# MSP_Telemetry.net
KiCad netlist of a schematic drawn in Altium Designer
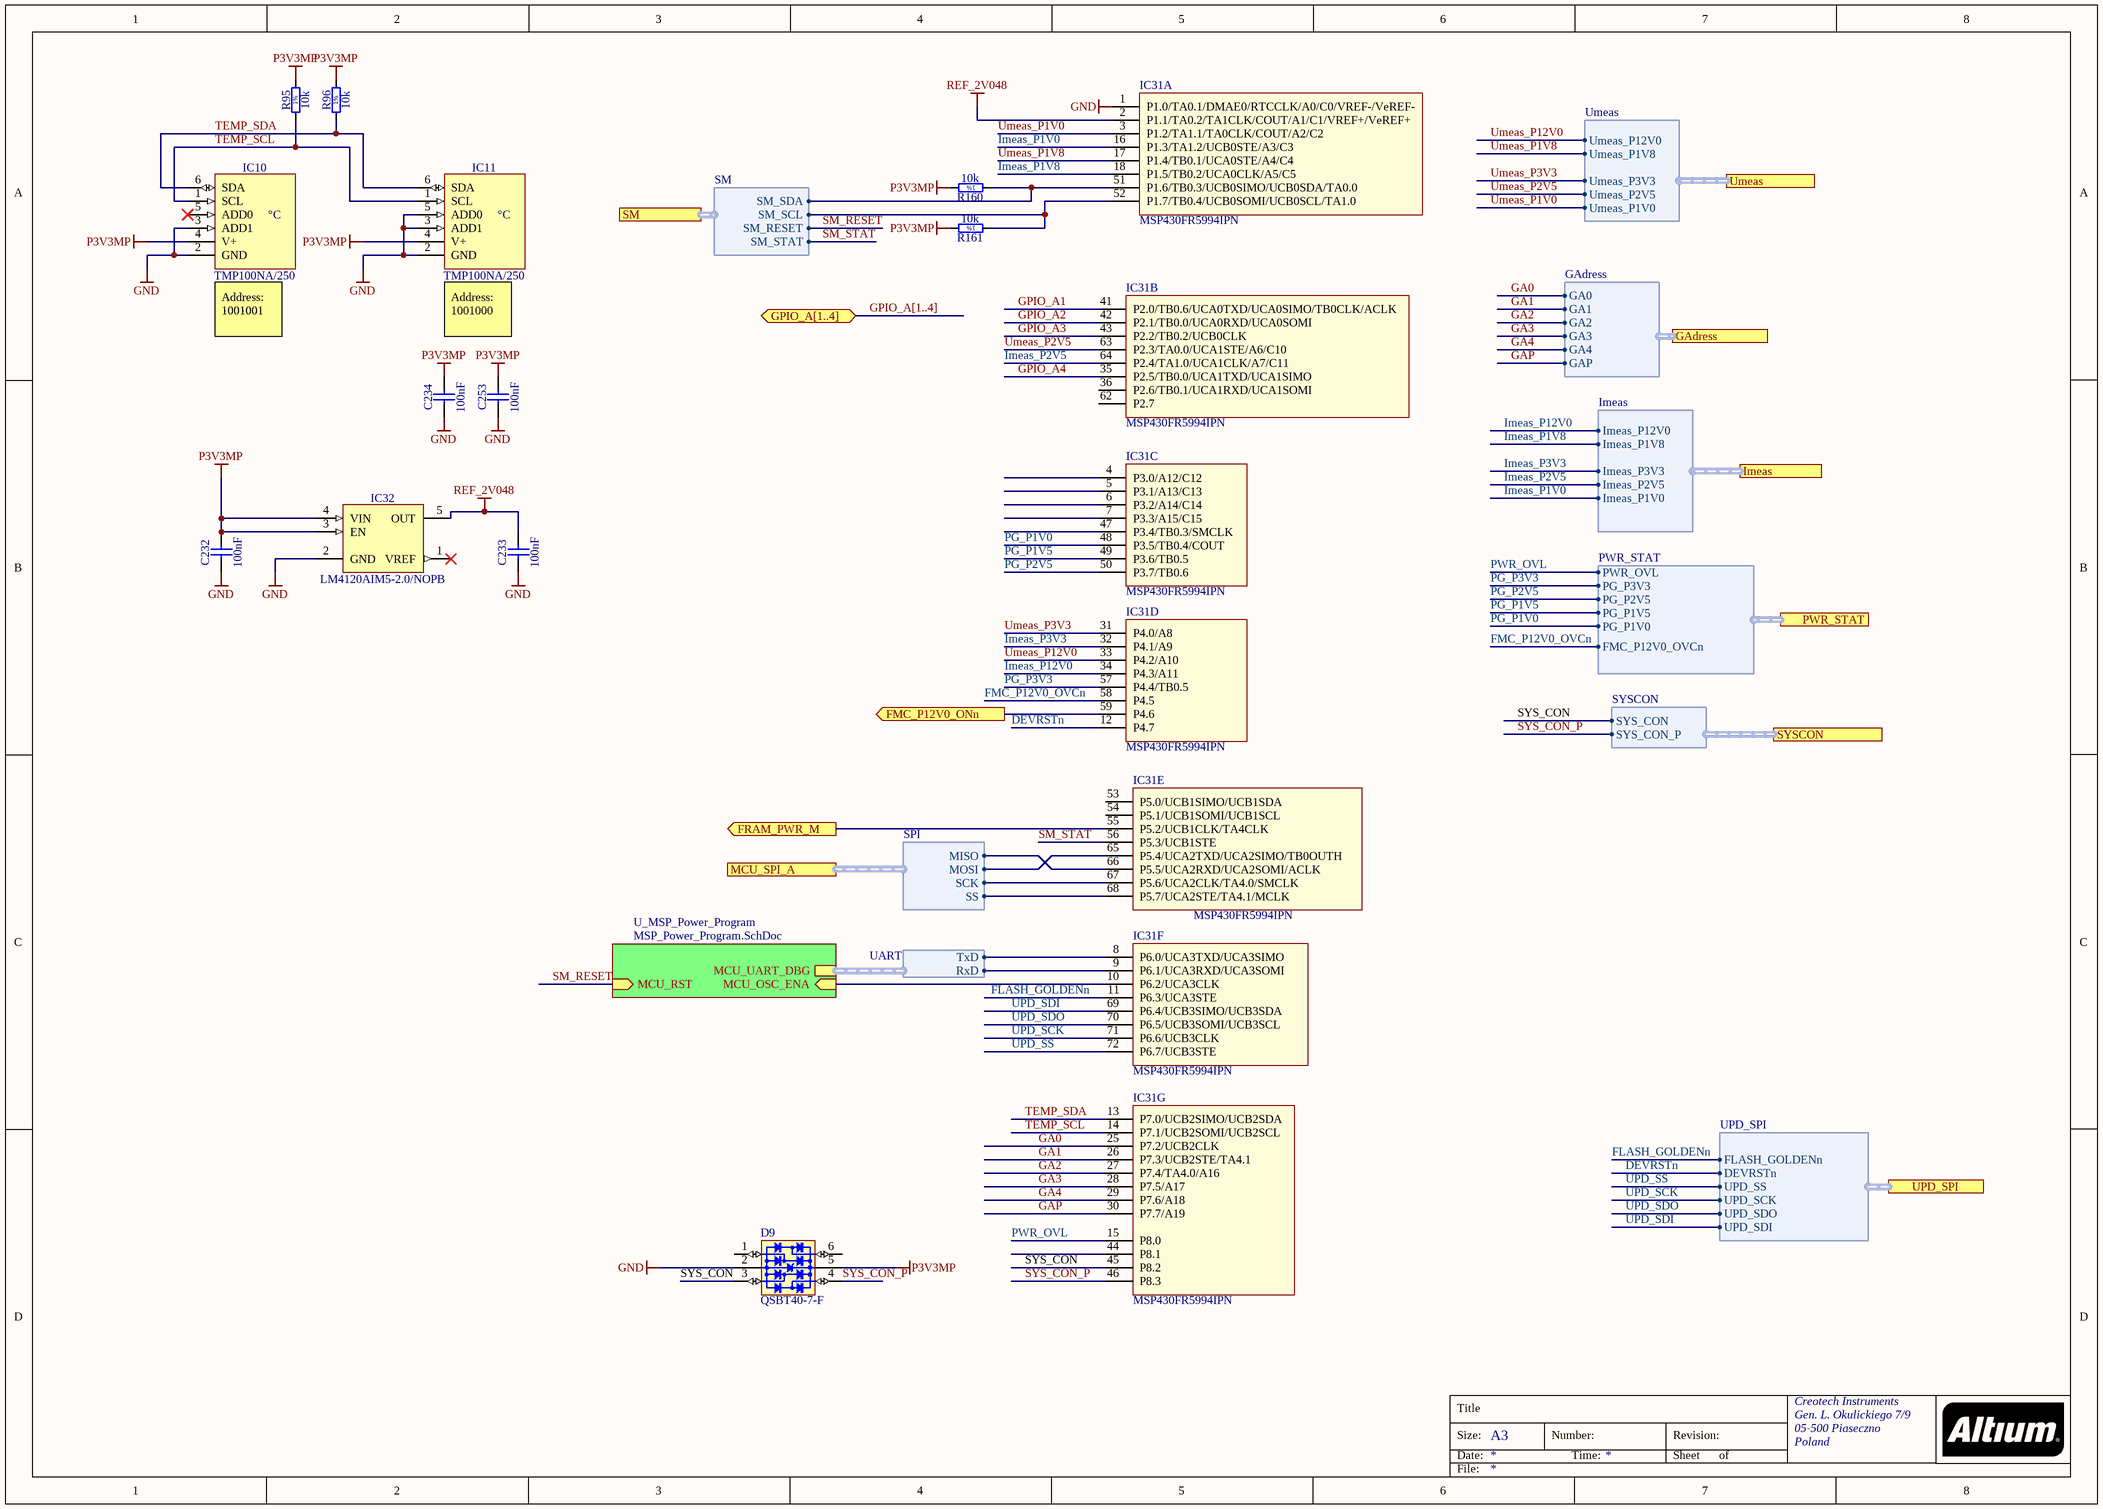
[diagram p0: MSP_Telemetry.SchDoc]

(export (version "E")
  (design (tool "Eeschema 10.0.6"))
  (components
    (comp (ref "C232")
      (value "100nF")
      (footprint "CAPC1005X55N")
      (description "Non-polarised capacitor")
      (fields
        (field (name "PART NUMBER") "CC0402_100NF_25V_10%_X7R_YUDEN_TMK105B7104KVHF")
        (field (name "VOLTAGE") "25V")
        (field (name "AUTHOR") "CERN DEM JLC")
      )
      (libsource (lib "Capacitors") (part "Capacitor - non polarized"))
    )
    (comp (ref "C233")
      (value "100nF")
      (footprint "CAPC1005X55N")
      (description "Non-polarised capacitor")
      (fields
        (field (name "PART NUMBER") "CC0402_100NF_25V_10%_X7R_YUDEN_TMK105B7104KVHF")
        (field (name "VOLTAGE") "25V")
        (field (name "AUTHOR") "CERN DEM JLC")
      )
      (libsource (lib "Capacitors") (part "Capacitor - non polarized"))
    )
    (comp (ref "C234")
      (value "100nF")
      (footprint "CAPC1005X55N")
      (description "Non-polarised capacitor")
      (fields
        (field (name "PART NUMBER") "CC0402_100NF_25V_10%_X7R_YUDEN_TMK105B7104KVHF")
        (field (name "VOLTAGE") "25V")
        (field (name "AUTHOR") "CERN DEM JLC")
      )
      (libsource (lib "Capacitors") (part "Capacitor - non polarized"))
    )
    (comp (ref "C253")
      (value "100nF")
      (footprint "CAPC1005X55N")
      (description "Non-polarised capacitor")
      (fields
        (field (name "PART NUMBER") "CC0402_100NF_25V_10%_X7R_YUDEN_TMK105B7104KVHF")
        (field (name "VOLTAGE") "25V")
        (field (name "AUTHOR") "CERN DEM JLC")
      )
      (libsource (lib "Capacitors") (part "Capacitor - non polarized"))
    )
    (comp (ref "D9")
      (value "QSBT40-7-F")
      (footprint "SOT65P210X110-6N")
      (libsource (lib "LIBRARY_SCH") (part "D_TVS_QSBT40-7-F"))
    )
    (comp (ref "IC10")
      (value "TMP100NA/250")
      (footprint "SOT95P280X145-6N")
      (description "Digital Temperature Sensor with I2C Interface")
      (fields (field (name "MANUFACTURER") "TEXAS INSTRUMENTS") (field (name "AUTHOR") "CERN DEM JLC"))
      (libsource (lib "ICs And Semiconductors") (part "TMP100"))
    )
    (comp (ref "IC11")
      (value "TMP100NA/250")
      (footprint "SOT95P280X145-6N")
      (description "Digital Temperature Sensor with I2C Interface")
      (fields (field (name "MANUFACTURER") "TEXAS INSTRUMENTS") (field (name "AUTHOR") "CERN DEM JLC"))
      (libsource (lib "ICs And Semiconductors") (part "TMP100"))
    )
    (comp (ref "IC31")
      (value "MSP430FR5994IPN")
      (footprint "PQFP50P1400X1400-80N")
      (fields (field (name "MANUFACTURER") "TI"))
      (libsource (lib "LIBRARY_SCH") (part "UPC_MSP430FR5994IPN"))
    )
    (comp (ref "IC32")
      (value "LM4120AIM5-2.0/NOPB")
      (footprint "SOT95P280X145-5N")
      (description "Precision Micropower Low Dropout Voltage Reference")
      (fields (field (name "MANUFACTURER") "TEXAS INSTRUMENTS") (field (name "AUTHOR") "CERN DEM JMW"))
      (libsource (lib "ICs And Semiconductors") (part "LM4120"))
    )
    (comp (ref "R95")
      (value "10k")
      (footprint "RESC1005X40N")
      (description "Resistor - 1%")
      (fields
        (field (name "PART NUMBER") "R0402_10K_1%_0.0625W_100PPM")
        (field (name "POWER") "0.0625W")
        (field (name "AUTHOR") "CERN DEM JLC")
      )
      (libsource (lib "Resistors") (part "Resistor - 1%"))
    )
    (comp (ref "R96")
      (value "10k")
      (footprint "RESC1005X40N")
      (description "Resistor - 1%")
      (fields
        (field (name "PART NUMBER") "R0402_10K_1%_0.0625W_100PPM")
        (field (name "POWER") "0.0625W")
        (field (name "AUTHOR") "CERN DEM JLC")
      )
      (libsource (lib "Resistors") (part "Resistor - 1%"))
    )
    (comp (ref "R160")
      (value "10k")
      (footprint "RESC1005X40N")
      (description "Resistor - 1%")
      (fields
        (field (name "PART NUMBER") "R0402_10K_1%_0.0625W_100PPM")
        (field (name "POWER") "0.0625W")
        (field (name "AUTHOR") "CERN DEM JLC")
      )
      (libsource (lib "Resistors") (part "Resistor - 1%"))
    )
    (comp (ref "R161")
      (value "10k")
      (footprint "RESC1005X40N")
      (description "Resistor - 1%")
      (fields
        (field (name "PART NUMBER") "R0402_10K_1%_0.0625W_100PPM")
        (field (name "POWER") "0.0625W")
        (field (name "AUTHOR") "CERN DEM JLC")
      )
      (libsource (lib "Resistors") (part "Resistor - 1%"))
    )
  )
  (nets
    (net (code "10") (name "/DEVRSTn") (class "Default")
      (node (ref "IC31") (pin "12") (pinfunction "P4.7_12") (pintype "passive"))
    )
    (net (code "11") (name "/FLASH_GOLDENn") (class "Default")
      (node (ref "IC31") (pin "11") (pinfunction "P6.3/UCA3STE_11") (pintype "passive"))
    )
    (net (code "12") (name "/FMC_P12V0_ONn") (class "Default")
      (node (ref "IC31") (pin "59") (pinfunction "P4.6_59") (pintype "passive"))
    )
    (net (code "13") (name "/FMC_P12V0_OVCn") (class "Default")
      (node (ref "IC31") (pin "58") (pinfunction "P4.5_58") (pintype "passive"))
    )
    (net (code "14") (name "/FRAM_PWR_M") (class "Default")
      (node (ref "IC31") (pin "55") (pinfunction "P5.2/UCB1CLK/TA4CLK_55") (pintype "passive"))
    )
    (net (code "15") (name "/GA0") (class "Default")
      (node (ref "IC31") (pin "25") (pinfunction "P7.2/UCB2CLK_25") (pintype "passive"))
    )
    (net (code "16") (name "/GA1") (class "Default")
      (node (ref "IC31") (pin "26") (pinfunction "P7.3/UCB2STE/TA4.1_26") (pintype "passive"))
    )
    (net (code "17") (name "/GA2") (class "Default")
      (node (ref "IC31") (pin "27") (pinfunction "P7.4/TA4.0/A16_27") (pintype "passive"))
    )
    (net (code "18") (name "/GA3") (class "Default")
      (node (ref "IC31") (pin "28") (pinfunction "P7.5/A17_28") (pintype "passive"))
    )
    (net (code "19") (name "/GA4") (class "Default")
      (node (ref "IC31") (pin "29") (pinfunction "P7.6/A18_29") (pintype "passive"))
    )
    (net (code "20") (name "/GAP") (class "Default")
      (node (ref "IC31") (pin "30") (pinfunction "P7.7/A19_30") (pintype "passive"))
    )
    (net (code "21") (name "/GPIO_A1") (class "Default")
      (node (ref "IC31") (pin "41") (pinfunction "P2.0/TB0.6/UCA0TXD/UCA0SIMO/TB0CLK/ACLK_41") (pintype "passive"))
    )
    (net (code "22") (name "/GPIO_A2") (class "Default")
      (node (ref "IC31") (pin "42") (pinfunction "P2.1/TB0.0/UCA0RXD/UCA0SOMI_42") (pintype "passive"))
    )
    (net (code "23") (name "/GPIO_A3") (class "Default")
      (node (ref "IC31") (pin "43") (pinfunction "P2.2/TB0.2/UCB0CLK_43") (pintype "passive"))
    )
    (net (code "24") (name "/GPIO_A4") (class "Default")
      (node (ref "IC31") (pin "35") (pinfunction "P2.5/TB0.0/UCA1TXD/UCA1SIMO_35") (pintype "passive"))
    )
    (net (code "26") (name "/Imeas_P1V0") (class "Default")
      (node (ref "IC31") (pin "16") (pinfunction "P1.3/TA1.2/UCB0STE/A3/C3_16") (pintype "passive"))
    )
    (net (code "27") (name "/Imeas_P1V8") (class "Default")
      (node (ref "IC31") (pin "18") (pinfunction "P1.5/TB0.2/UCA0CLK/A5/C5_18") (pintype "passive"))
    )
    (net (code "28") (name "/Imeas_P2V5") (class "Default")
      (node (ref "IC31") (pin "64") (pinfunction "P2.4/TA1.0/UCA1CLK/A7/C11_64") (pintype "passive"))
    )
    (net (code "29") (name "/Imeas_P3V3") (class "Default")
      (node (ref "IC31") (pin "32") (pinfunction "P4.1/A9_32") (pintype "passive"))
    )
    (net (code "30") (name "/Imeas_P12V0") (class "Default")
      (node (ref "IC31") (pin "34") (pinfunction "P4.3/A11_34") (pintype "passive"))
    )
    (net (code "31") (name "/MCU_OSC_ENA") (class "Default")
      (node (ref "IC31") (pin "10") (pinfunction "P6.2/UCA3CLK_10") (pintype "passive"))
    )
    (net (code "32") (name "/MISO") (class "Default")
      (node (ref "IC31") (pin "66") (pinfunction "P5.5/UCA2RXD/UCA2SOMI/ACLK_66") (pintype "passive"))
    )
    (net (code "33") (name "/MOSI") (class "Default")
      (node (ref "IC31") (pin "65") (pinfunction "P5.4/UCA2TXD/UCA2SIMO/TB0OUTH_65") (pintype "passive"))
    )
    (net (code "34") (name "/PG_P1V0") (class "Default")
      (node (ref "IC31") (pin "48") (pinfunction "P3.5/TB0.4/COUT_48") (pintype "passive"))
    )
    (net (code "35") (name "/PG_P1V5") (class "Default")
      (node (ref "IC31") (pin "49") (pinfunction "P3.6/TB0.5_49") (pintype "passive"))
    )
    (net (code "36") (name "/PG_P2V5") (class "Default")
      (node (ref "IC31") (pin "50") (pinfunction "P3.7/TB0.6_50") (pintype "passive"))
    )
    (net (code "37") (name "/PG_P3V3") (class "Default")
      (node (ref "IC31") (pin "57") (pinfunction "P4.4/TB0.5_57") (pintype "passive"))
    )
    (net (code "38") (name "/PWR_OVL") (class "Default")
      (node (ref "IC31") (pin "15") (pinfunction "P8.0_15") (pintype "passive"))
    )
    (net (code "39") (name "/RxD") (class "Default")
      (node (ref "IC31") (pin "9") (pinfunction "P6.1/UCA3RXD/UCA3SOMI_9") (pintype "passive"))
    )
    (net (code "40") (name "/SCK") (class "Default")
      (node (ref "IC31") (pin "67") (pinfunction "P5.6/UCA2CLK/TA4.0/SMCLK_67") (pintype "passive"))
    )
    (net (code "42") (name "/SM_SCL") (class "Default")
      (node (ref "IC31") (pin "52") (pinfunction "P1.7/TB0.4/UCB0SOMI/UCB0SCL/TA1.0_52") (pintype "passive"))
      (node (ref "R161") (pin "1") (pinfunction "1_1") (pintype "passive"))
    )
    (net (code "43") (name "/SM_SDA") (class "Default")
      (node (ref "IC31") (pin "51") (pinfunction "P1.6/TB0.3/UCB0SIMO/UCB0SDA/TA0.0_51") (pintype "passive"))
      (node (ref "R160") (pin "1") (pinfunction "1_1") (pintype "passive"))
    )
    (net (code "44") (name "/SM_STAT") (class "Default")
      (node (ref "IC31") (pin "56") (pinfunction "P5.3/UCB1STE_56") (pintype "passive"))
    )
    (net (code "45") (name "/SS") (class "Default")
      (node (ref "IC31") (pin "68") (pinfunction "P5.7/UCA2STE/TA4.1/MCLK_68") (pintype "passive"))
    )
    (net (code "46") (name "/SYS_CON") (class "Default")
      (node (ref "D9") (pin "3") (pinfunction "I/O2_3") (pintype "bidirectional"))
      (node (ref "IC31") (pin "45") (pinfunction "P8.2_45") (pintype "passive"))
    )
    (net (code "47") (name "/SYS_CON_P") (class "Default")
      (node (ref "D9") (pin "4") (pinfunction "I/O3_4") (pintype "bidirectional"))
      (node (ref "IC31") (pin "46") (pinfunction "P8.3_46") (pintype "passive"))
    )
    (net (code "48") (name "/TEMP_SCL") (class "Default")
      (node (ref "IC10") (pin "1") (pinfunction "SCL_1") (pintype "input"))
      (node (ref "IC11") (pin "1") (pinfunction "SCL_1") (pintype "input"))
      (node (ref "IC31") (pin "14") (pinfunction "P7.1/UCB2SOMI/UCB2SCL_14") (pintype "passive"))
      (node (ref "R95") (pin "1") (pinfunction "1_1") (pintype "passive"))
    )
    (net (code "49") (name "/TEMP_SDA") (class "Default")
      (node (ref "IC10") (pin "6") (pinfunction "SDA_6") (pintype "bidirectional"))
      (node (ref "IC11") (pin "6") (pinfunction "SDA_6") (pintype "bidirectional"))
      (node (ref "IC31") (pin "13") (pinfunction "P7.0/UCB2SIMO/UCB2SDA_13") (pintype "passive"))
      (node (ref "R96") (pin "1") (pinfunction "1_1") (pintype "passive"))
    )
    (net (code "50") (name "/TxD") (class "Default")
      (node (ref "IC31") (pin "8") (pinfunction "P6.0/UCA3TXD/UCA3SIMO_8") (pintype "passive"))
    )
    (net (code "51") (name "/UPD_SCK") (class "Default")
      (node (ref "IC31") (pin "71") (pinfunction "P6.6/UCB3CLK_71") (pintype "passive"))
    )
    (net (code "52") (name "/UPD_SDI") (class "Default")
      (node (ref "IC31") (pin "69") (pinfunction "P6.4/UCB3SIMO/UCB3SDA_69") (pintype "passive"))
    )
    (net (code "53") (name "/UPD_SDO") (class "Default")
      (node (ref "IC31") (pin "70") (pinfunction "P6.5/UCB3SOMI/UCB3SCL_70") (pintype "passive"))
    )
    (net (code "54") (name "/UPD_SS") (class "Default")
      (node (ref "IC31") (pin "72") (pinfunction "P6.7/UCB3STE_72") (pintype "passive"))
    )
    (net (code "55") (name "/Umeas_P1V0") (class "Default")
      (node (ref "IC31") (pin "3") (pinfunction "P1.2/TA1.1/TA0CLK/COUT/A2/C2_3") (pintype "passive"))
    )
    (net (code "56") (name "/Umeas_P1V8") (class "Default")
      (node (ref "IC31") (pin "17") (pinfunction "P1.4/TB0.1/UCA0STE/A4/C4_17") (pintype "passive"))
    )
    (net (code "57") (name "/Umeas_P2V5") (class "Default")
      (node (ref "IC31") (pin "63") (pinfunction "P2.3/TA0.0/UCA1STE/A6/C10_63") (pintype "passive"))
    )
    (net (code "58") (name "/Umeas_P3V3") (class "Default")
      (node (ref "IC31") (pin "31") (pinfunction "P4.0/A8_31") (pintype "passive"))
    )
    (net (code "59") (name "/Umeas_P12V0") (class "Default")
      (node (ref "IC31") (pin "33") (pinfunction "P4.2/A10_33") (pintype "passive"))
    )
    (net (code "69") (name "GND") (class "Default")
      (node (ref "C232") (pin "1") (pinfunction "1_1") (pintype "passive"))
      (node (ref "C233") (pin "1") (pinfunction "1_1") (pintype "passive"))
      (node (ref "C234") (pin "1") (pinfunction "1_1") (pintype "passive"))
      (node (ref "C253") (pin "1") (pinfunction "1_1") (pintype "passive"))
      (node (ref "D9") (pin "2") (pinfunction "GND_2") (pintype "power_in"))
      (node (ref "IC10") (pin "2") (pinfunction "GND_2") (pintype "power_in"))
      (node (ref "IC10") (pin "3") (pinfunction "ADD1_3") (pintype "input"))
      (node (ref "IC11") (pin "2") (pinfunction "GND_2") (pintype "power_in"))
      (node (ref "IC11") (pin "3") (pinfunction "ADD1_3") (pintype "input"))
      (node (ref "IC11") (pin "5") (pinfunction "ADD0_5") (pintype "input"))
      (node (ref "IC31") (pin "1") (pinfunction "P1.0/TA0.1/DMAE0/RTCCLK/A0/C0/VREF-/VeREF-_1") (pintype "passive"))
      (node (ref "IC32") (pin "2") (pinfunction "GND_2") (pintype "power_in"))
    )
    (net (code "70") (name "P3V3MP") (class "Default")
      (node (ref "C232") (pin "2") (pinfunction "2_2") (pintype "passive"))
      (node (ref "C234") (pin "2") (pinfunction "2_2") (pintype "passive"))
      (node (ref "C253") (pin "2") (pinfunction "2_2") (pintype "passive"))
      (node (ref "D9") (pin "5") (pinfunction "VBUS_5") (pintype "power_in"))
      (node (ref "IC10") (pin "4") (pinfunction "V+_4") (pintype "power_in"))
      (node (ref "IC11") (pin "4") (pinfunction "V+_4") (pintype "power_in"))
      (node (ref "IC32") (pin "3") (pinfunction "EN_3") (pintype "input"))
      (node (ref "IC32") (pin "4") (pinfunction "VIN_4") (pintype "input"))
      (node (ref "R160") (pin "2") (pinfunction "2_2") (pintype "passive"))
      (node (ref "R161") (pin "2") (pinfunction "2_2") (pintype "passive"))
      (node (ref "R95") (pin "2") (pinfunction "2_2") (pintype "passive"))
      (node (ref "R96") (pin "2") (pinfunction "2_2") (pintype "passive"))
    )
    (net (code "71") (name "REF_2V048") (class "Default")
      (node (ref "C233") (pin "2") (pinfunction "2_2") (pintype "passive"))
      (node (ref "IC31") (pin "2") (pinfunction "P1.1/TA0.2/TA1CLK/COUT/A1/C1/VREF+/VeREF+_2") (pintype "passive"))
      (node (ref "IC32") (pin "5") (pinfunction "OUT_5") (pintype "power_in"))
    )
    (net (code "72") (name "unconnected-(D9-I{slash}O1-Pad1)") (class "Default")
      (node (ref "D9") (pin "1") (pinfunction "I/O1_1") (pintype "bidirectional"))
    )
    (net (code "73") (name "unconnected-(D9-I{slash}O4-Pad6)") (class "Default")
      (node (ref "D9") (pin "6") (pinfunction "I/O4_6") (pintype "bidirectional"))
    )
    (net (code "74") (name "unconnected-(IC10-ADD0-Pad5)") (class "Default")
      (node (ref "IC10") (pin "5") (pinfunction "ADD0_5") (pintype "input+no_connect"))
    )
    (net (code "75") (name "unconnected-(IC31B-P2.6{slash}TB0.1{slash}UCA1RXD{slash}UCA1SOMI-Pad36)") (class "Default")
      (node (ref "IC31") (pin "36") (pinfunction "P2.6/TB0.1/UCA1RXD/UCA1SOMI_36") (pintype "passive"))
    )
    (net (code "76") (name "unconnected-(IC31B-P2.7-Pad62)") (class "Default")
      (node (ref "IC31") (pin "62") (pinfunction "P2.7_62") (pintype "passive"))
    )
    (net (code "77") (name "unconnected-(IC31C-P3.0{slash}A12{slash}C12-Pad4)") (class "Default")
      (node (ref "IC31") (pin "4") (pinfunction "P3.0/A12/C12_4") (pintype "passive"))
    )
    (net (code "78") (name "unconnected-(IC31C-P3.1{slash}A13{slash}C13-Pad5)") (class "Default")
      (node (ref "IC31") (pin "5") (pinfunction "P3.1/A13/C13_5") (pintype "passive"))
    )
    (net (code "79") (name "unconnected-(IC31C-P3.2{slash}A14{slash}C14-Pad6)") (class "Default")
      (node (ref "IC31") (pin "6") (pinfunction "P3.2/A14/C14_6") (pintype "passive"))
    )
    (net (code "80") (name "unconnected-(IC31C-P3.3{slash}A15{slash}C15-Pad7)") (class "Default")
      (node (ref "IC31") (pin "7") (pinfunction "P3.3/A15/C15_7") (pintype "passive"))
    )
    (net (code "81") (name "unconnected-(IC31C-P3.4{slash}TB0.3{slash}SMCLK-Pad47)") (class "Default")
      (node (ref "IC31") (pin "47") (pinfunction "P3.4/TB0.3/SMCLK_47") (pintype "passive"))
    )
    (net (code "82") (name "unconnected-(IC31E-P5.0{slash}UCB1SIMO{slash}UCB1SDA-Pad53)") (class "Default")
      (node (ref "IC31") (pin "53") (pinfunction "P5.0/UCB1SIMO/UCB1SDA_53") (pintype "passive"))
    )
    (net (code "83") (name "unconnected-(IC31E-P5.1{slash}UCB1SOMI{slash}UCB1SCL-Pad54)") (class "Default")
      (node (ref "IC31") (pin "54") (pinfunction "P5.1/UCB1SOMI/UCB1SCL_54") (pintype "passive"))
    )
    (net (code "84") (name "unconnected-(IC31G-P8.1-Pad44)") (class "Default")
      (node (ref "IC31") (pin "44") (pinfunction "P8.1_44") (pintype "passive"))
    )
    (net (code "85") (name "unconnected-(IC32-VREF-Pad1)") (class "Default")
      (node (ref "IC32") (pin "1") (pinfunction "VREF_1") (pintype "output+no_connect"))
    )
  )
)
